# gps-tracker.net
KiCad netlist of a schematic drawn in EAGLE
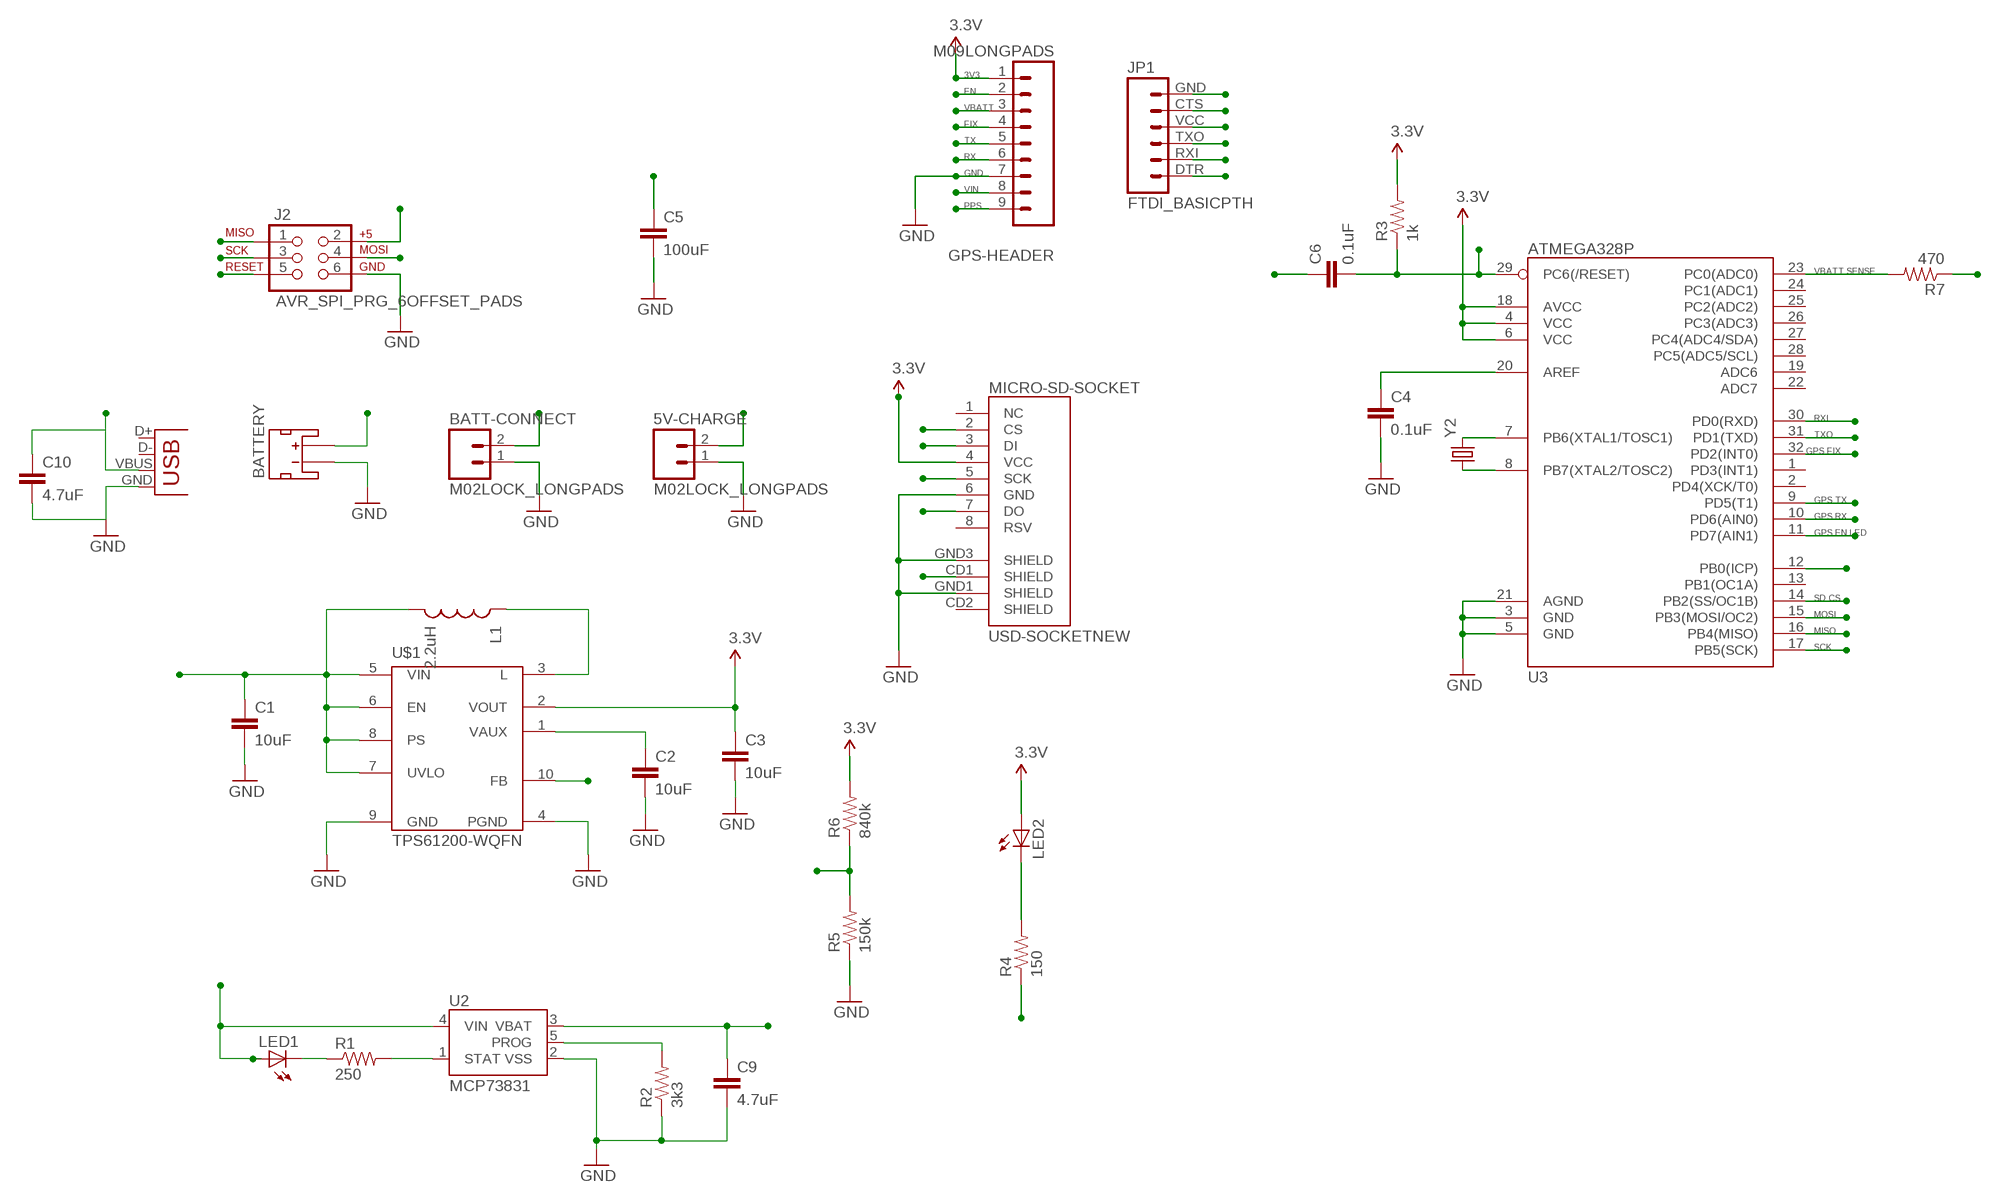
[diagram p0: schematic, sheet 1]

(export (version "E")
  (design (tool "Eeschema 10.0.6"))
  (components
    (comp (ref "5V-CHARGE")
      (value "M02LOCK_LONGPADS")
      (footprint "eagle-import:1X02_LOCK_LONGPADS")
      (libsource (lib "eagle-import") (part "M02LOCK_LONGPADS"))
    )
    (comp (ref "BATT-CONNECT")
      (value "M02LOCK_LONGPADS")
      (footprint "eagle-import:1X02_LOCK_LONGPADS")
      (libsource (lib "eagle-import") (part "M02LOCK_LONGPADS"))
    )
    (comp (ref "BATTERY")
      (value "JST_2MM_MALE")
      (footprint "eagle-import:JST-2-SMD")
      (libsource (lib "eagle-import") (part "JST_2MM_MALE"))
    )
    (comp (ref "C1")
      (value "10uF")
      (footprint "eagle-import:1206")
      (libsource (lib "eagle-import") (part "CAP1206"))
    )
    (comp (ref "C2")
      (value "10uF")
      (footprint "eagle-import:1206")
      (libsource (lib "eagle-import") (part "CAP1206"))
    )
    (comp (ref "C3")
      (value "10uF")
      (footprint "eagle-import:1206")
      (libsource (lib "eagle-import") (part "CAP1206"))
    )
    (comp (ref "C4")
      (value "0.1uF")
      (footprint "eagle-import:0603-CAP")
      (libsource (lib "eagle-import") (part "SparkFun-Capacitors_CAP0603-CAP"))
    )
    (comp (ref "C5")
      (value "100uF")
      (footprint "eagle-import:1206")
      (libsource (lib "eagle-import") (part "SparkFun-Capacitors_CAP1206"))
    )
    (comp (ref "C6")
      (value "0.1uF")
      (footprint "eagle-import:0603-CAP")
      (libsource (lib "eagle-import") (part "SparkFun-Capacitors_CAP0603-CAP"))
    )
    (comp (ref "C9")
      (value "4.7uF")
      (footprint "eagle-import:1206")
      (libsource (lib "eagle-import") (part "CAP1206"))
    )
    (comp (ref "C10")
      (value "4.7uF")
      (footprint "eagle-import:1206")
      (libsource (lib "eagle-import") (part "CAP1206"))
    )
    (comp (ref "GPS-HEADER")
      (value "M09LONGPADS")
      (footprint "eagle-import:1X09_LONGPADS")
      (libsource (lib "eagle-import") (part "M09LONGPADS"))
    )
    (comp (ref "J2")
      (value "AVR_SPI_PRG_6OFFSET_PADS")
      (footprint "eagle-import:2X3_OFFSET")
      (libsource (lib "eagle-import") (part "AVR_SPI_PRG_6OFFSET_PADS"))
    )
    (comp (ref "JP1")
      (value "FTDI_BASICPTH")
      (footprint "eagle-import:FTDI_BASIC")
      (libsource (lib "eagle-import") (part "FTDI_BASICPTH"))
    )
    (comp (ref "L1")
      (value "2.2uH")
      (footprint "eagle-import:CDRH3D28")
      (libsource (lib "eagle-import") (part "INDUCTOR-"))
    )
    (comp (ref "LED1")
      (value "LED0603")
      (footprint "eagle-import:LED-0603")
      (libsource (lib "eagle-import") (part "LED0603"))
    )
    (comp (ref "LED2")
      (value "LED5MM")
      (footprint "eagle-import:LED5MM")
      (libsource (lib "eagle-import") (part "SparkFun-LED_LED5MM"))
    )
    (comp (ref "MICRO-SD-SOCKET")
      (value "USD-SOCKETNEW")
      (footprint "eagle-import:MICRO-SD-SOCKET-PP")
      (libsource (lib "eagle-import") (part "USD-SOCKETNEW"))
    )
    (comp (ref "R1")
      (value "250")
      (footprint "eagle-import:0603-RES")
      (libsource (lib "eagle-import") (part "RESISTOR0603-RES"))
    )
    (comp (ref "R2")
      (value "3k3")
      (footprint "eagle-import:0603-RES")
      (libsource (lib "eagle-import") (part "RESISTOR0603-RES"))
    )
    (comp (ref "R3")
      (value "1k")
      (footprint "eagle-import:0805")
      (libsource (lib "eagle-import") (part "RESISTOR0805-RES"))
    )
    (comp (ref "R4")
      (value "150")
      (footprint "eagle-import:0805")
      (libsource (lib "eagle-import") (part "RESISTOR0805-RES"))
    )
    (comp (ref "R5")
      (value "150k")
      (footprint "eagle-import:0603-RES")
      (libsource (lib "eagle-import") (part "RESISTOR0603-RES"))
    )
    (comp (ref "R6")
      (value "840k")
      (footprint "eagle-import:0603-RES")
      (libsource (lib "eagle-import") (part "RESISTOR0603-RES"))
    )
    (comp (ref "R7")
      (value "470")
      (footprint "eagle-import:0805")
      (libsource (lib "eagle-import") (part "RESISTOR0805-RES"))
    )
    (comp (ref "U$1")
      (value "TPS61200-WQFN")
      (footprint "eagle-import:QFN-10")
      (libsource (lib "eagle-import") (part "TPS61200-WQFN"))
    )
    (comp (ref "U2")
      (value "MCP73831")
      (footprint "eagle-import:SOT23-5")
      (libsource (lib "eagle-import") (part "MCP73831"))
    )
    (comp (ref "U3")
      (value "ATMEGA328P")
      (footprint "eagle-import:TQFP32-08")
      (libsource (lib "eagle-import") (part "ATMEGA328_SMT"))
    )
    (comp (ref "X1")
      (value "USBSMD")
      (footprint "eagle-import:USB-MINIB")
      (libsource (lib "eagle-import") (part "USBSMD"))
    )
    (comp (ref "Y2")
      (value "CRYSTAL5X3")
      (footprint "eagle-import:CRYSTAL-SMD-5X3")
      (libsource (lib "eagle-import") (part "CRYSTAL5X3"))
    )
  )
  (nets
    (net (code "1") (name "/BATT_LED") (class "Default")
      (node (ref "R4") (pin "1") (pinfunction "1_1") (pintype "passive"))
      (node (ref "U3") (pin "12") (pinfunction "PB0(ICP)_12") (pintype "bidirectional"))
    )
    (net (code "2") (name "/DTR") (class "Default")
      (node (ref "C6") (pin "1") (pinfunction "1_1") (pintype "passive"))
      (node (ref "JP1") (pin "DTR") (pinfunction "1_DTR") (pintype "passive"))
    )
    (net (code "3") (name "/FB") (class "Default")
      (node (ref "R5") (pin "2") (pinfunction "2_2") (pintype "passive"))
      (node (ref "R6") (pin "1") (pinfunction "1_1") (pintype "passive"))
      (node (ref "U$1") (pin "10") (pinfunction "FB_10") (pintype "bidirectional"))
    )
    (net (code "4") (name "/GPS_FIX") (class "Default")
      (node (ref "GPS-HEADER") (pin "4") (pinfunction "4_4") (pintype "passive"))
      (node (ref "U3") (pin "32") (pinfunction "PD2(INT0)_32") (pintype "bidirectional"))
    )
    (net (code "5") (name "/GPS_RX") (class "Default")
      (node (ref "GPS-HEADER") (pin "6") (pinfunction "6_6") (pintype "passive"))
      (node (ref "U3") (pin "9") (pinfunction "PD5(T1)_9") (pintype "bidirectional"))
    )
    (net (code "6") (name "/GPS_TX") (class "Default")
      (node (ref "GPS-HEADER") (pin "5") (pinfunction "5_5") (pintype "passive"))
      (node (ref "U3") (pin "10") (pinfunction "PD6(AIN0)_10") (pintype "bidirectional"))
    )
    (net (code "7") (name "/MISO") (class "Default")
      (node (ref "J2") (pin "1") (pinfunction "1_1") (pintype "passive"))
      (node (ref "MICRO-SD-SOCKET") (pin "7") (pinfunction "DO_7") (pintype "bidirectional"))
      (node (ref "U3") (pin "16") (pinfunction "PB4(MISO)_16") (pintype "bidirectional"))
    )
    (net (code "8") (name "/MOSI") (class "Default")
      (node (ref "J2") (pin "4") (pinfunction "4_4") (pintype "passive"))
      (node (ref "MICRO-SD-SOCKET") (pin "3") (pinfunction "DI_3") (pintype "bidirectional"))
      (node (ref "U3") (pin "15") (pinfunction "PB3(MOSI/OC2)_15") (pintype "bidirectional"))
    )
    (net (code "9") (name "/RXI") (class "Default")
      (node (ref "JP1") (pin "TXO") (pinfunction "3_TXO") (pintype "passive"))
      (node (ref "U3") (pin "31") (pinfunction "PD1(TXD)_31") (pintype "bidirectional"))
    )
    (net (code "10") (name "/SCK") (class "Default")
      (node (ref "J2") (pin "3") (pinfunction "3_3") (pintype "passive"))
      (node (ref "MICRO-SD-SOCKET") (pin "5") (pinfunction "SCK_5") (pintype "bidirectional"))
      (node (ref "U3") (pin "17") (pinfunction "PB5(SCK)_17") (pintype "bidirectional"))
    )
    (net (code "11") (name "/SD_CS") (class "Default")
      (node (ref "MICRO-SD-SOCKET") (pin "2") (pinfunction "CS_2") (pintype "bidirectional"))
      (node (ref "U3") (pin "14") (pinfunction "PB2(SS/OC1B)_14") (pintype "bidirectional"))
    )
    (net (code "12") (name "/TXO") (class "Default")
      (node (ref "JP1") (pin "RXI") (pinfunction "2_RXI") (pintype "passive"))
      (node (ref "U3") (pin "30") (pinfunction "PD0(RXD)_30") (pintype "bidirectional"))
    )
    (net (code "13") (name "/VBATT") (class "Default")
      (node (ref "BATT-CONNECT") (pin "2") (pinfunction "2_2") (pintype "passive"))
      (node (ref "BATTERY") (pin "2") (pinfunction "+_2") (pintype "bidirectional"))
      (node (ref "C1") (pin "1") (pinfunction "1_1") (pintype "passive"))
      (node (ref "C5") (pin "1") (pinfunction "1_1") (pintype "passive"))
      (node (ref "C9") (pin "1") (pinfunction "1_1") (pintype "passive"))
      (node (ref "L1") (pin "2") (pinfunction "2_2") (pintype "passive"))
      (node (ref "R7") (pin "1") (pinfunction "1_1") (pintype "passive"))
      (node (ref "U$1") (pin "5") (pinfunction "VIN_5") (pintype "bidirectional"))
      (node (ref "U$1") (pin "6") (pinfunction "EN_6") (pintype "bidirectional"))
      (node (ref "U$1") (pin "7") (pinfunction "UVLO_7") (pintype "bidirectional"))
      (node (ref "U$1") (pin "8") (pinfunction "PS_8") (pintype "bidirectional"))
      (node (ref "U2") (pin "3") (pinfunction "VBAT_3") (pintype "power_in"))
    )
    (net (code "14") (name "/VUSB") (class "Default")
      (node (ref "5V-CHARGE") (pin "2") (pinfunction "2_2") (pintype "passive"))
      (node (ref "C10") (pin "1") (pinfunction "1_1") (pintype "passive"))
      (node (ref "LED1") (pin "A") (pinfunction "A_A") (pintype "passive"))
      (node (ref "U2") (pin "4") (pinfunction "VIN_4") (pintype "power_in"))
      (node (ref "X1") (pin "VBUS") (pinfunction "VBUS_VBUS") (pintype "bidirectional"))
    )
    (net (code "15") (name "/{slash}RESET") (class "Default")
      (node (ref "C6") (pin "2") (pinfunction "2_2") (pintype "passive"))
      (node (ref "J2") (pin "5") (pinfunction "5_5") (pintype "passive"))
      (node (ref "R3") (pin "1") (pinfunction "1_1") (pintype "passive"))
      (node (ref "U3") (pin "29") (pinfunction "PC6(/RESET)_29") (pintype "bidirectional"))
    )
    (net (code "16") (name "3.3V") (class "Default")
      (node (ref "C3") (pin "1") (pinfunction "1_1") (pintype "passive"))
      (node (ref "GPS-HEADER") (pin "1") (pinfunction "1_1") (pintype "passive"))
      (node (ref "LED2") (pin "A") (pinfunction "A_A") (pintype "passive"))
      (node (ref "MICRO-SD-SOCKET") (pin "4") (pinfunction "VCC_4") (pintype "bidirectional"))
      (node (ref "R3") (pin "2") (pinfunction "2_2") (pintype "passive"))
      (node (ref "R6") (pin "2") (pinfunction "2_2") (pintype "passive"))
      (node (ref "U$1") (pin "2") (pinfunction "VOUT_2") (pintype "bidirectional"))
      (node (ref "U3") (pin "18") (pinfunction "AVCC_18") (pintype "bidirectional"))
      (node (ref "U3") (pin "4") (pinfunction "VCC_4") (pintype "bidirectional"))
      (node (ref "U3") (pin "6") (pinfunction "VCC_6") (pintype "bidirectional"))
    )
    (net (code "17") (name "GND") (class "Default")
      (node (ref "5V-CHARGE") (pin "1") (pinfunction "1_1") (pintype "passive"))
      (node (ref "BATT-CONNECT") (pin "1") (pinfunction "1_1") (pintype "passive"))
      (node (ref "BATTERY") (pin "1") (pinfunction "-_1") (pintype "bidirectional"))
      (node (ref "C1") (pin "2") (pinfunction "2_2") (pintype "passive"))
      (node (ref "C10") (pin "2") (pinfunction "2_2") (pintype "passive"))
      (node (ref "C2") (pin "2") (pinfunction "2_2") (pintype "passive"))
      (node (ref "C3") (pin "2") (pinfunction "2_2") (pintype "passive"))
      (node (ref "C4") (pin "2") (pinfunction "2_2") (pintype "passive"))
      (node (ref "C5") (pin "2") (pinfunction "2_2") (pintype "passive"))
      (node (ref "C9") (pin "2") (pinfunction "2_2") (pintype "passive"))
      (node (ref "GPS-HEADER") (pin "7") (pinfunction "7_7") (pintype "passive"))
      (node (ref "J2") (pin "6") (pinfunction "6_6") (pintype "passive"))
      (node (ref "JP1") (pin "CTS") (pinfunction "5_CTS") (pintype "passive"))
      (node (ref "JP1") (pin "GND") (pinfunction "6_GND") (pintype "passive"))
      (node (ref "MICRO-SD-SOCKET") (pin "6") (pinfunction "GND_6") (pintype "bidirectional"))
      (node (ref "MICRO-SD-SOCKET") (pin "GND1") (pinfunction "SHIELD_GND1") (pintype "bidirectional"))
      (node (ref "MICRO-SD-SOCKET") (pin "GND3") (pinfunction "SHIELD_GND3") (pintype "bidirectional"))
      (node (ref "R2") (pin "1") (pinfunction "1_1") (pintype "passive"))
      (node (ref "R5") (pin "1") (pinfunction "1_1") (pintype "passive"))
      (node (ref "U$1") (pin "4") (pinfunction "PGND_4") (pintype "bidirectional"))
      (node (ref "U$1") (pin "9") (pinfunction "GND_9") (pintype "bidirectional"))
      (node (ref "U2") (pin "2") (pinfunction "VSS_2") (pintype "power_in"))
      (node (ref "U3") (pin "21") (pinfunction "AGND_21") (pintype "bidirectional"))
      (node (ref "U3") (pin "3") (pinfunction "GND_3") (pintype "bidirectional"))
      (node (ref "U3") (pin "5") (pinfunction "GND_5") (pintype "bidirectional"))
      (node (ref "X1") (pin "GND") (pinfunction "GND_GND") (pintype "bidirectional"))
    )
    (net (code "18") (name "Net-(LED1-PadC)") (class "Default")
      (node (ref "LED1") (pin "C") (pinfunction "C_C") (pintype "passive"))
      (node (ref "R1") (pin "1") (pinfunction "1_1") (pintype "passive"))
    )
    (net (code "19") (name "Net-(LED2-C)") (class "Default")
      (node (ref "LED2") (pin "K") (pinfunction "C_K") (pintype "passive"))
      (node (ref "R4") (pin "2") (pinfunction "2_2") (pintype "passive"))
    )
    (net (code "20") (name "Net-(U$1-L)") (class "Default")
      (node (ref "L1") (pin "1") (pinfunction "1_1") (pintype "passive"))
      (node (ref "U$1") (pin "3") (pinfunction "L_3") (pintype "bidirectional"))
    )
    (net (code "21") (name "Net-(U$1-VAUX)") (class "Default")
      (node (ref "C2") (pin "1") (pinfunction "1_1") (pintype "passive"))
      (node (ref "U$1") (pin "1") (pinfunction "VAUX_1") (pintype "bidirectional"))
    )
    (net (code "22") (name "Net-(U2-PROG)") (class "Default")
      (node (ref "R2") (pin "2") (pinfunction "2_2") (pintype "passive"))
      (node (ref "U2") (pin "5") (pinfunction "PROG_5") (pintype "input"))
    )
    (net (code "23") (name "Net-(U2-STAT)") (class "Default")
      (node (ref "R1") (pin "2") (pinfunction "2_2") (pintype "passive"))
      (node (ref "U2") (pin "1") (pinfunction "STAT_1") (pintype "output"))
    )
    (net (code "24") (name "Net-(U3-AREF)") (class "Default")
      (node (ref "C4") (pin "1") (pinfunction "1_1") (pintype "passive"))
      (node (ref "U3") (pin "20") (pinfunction "AREF_20") (pintype "bidirectional"))
    )
    (net (code "25") (name "Net-(U3-PB6(XTAL1{slash}TOSC1))") (class "Default")
      (node (ref "U3") (pin "7") (pinfunction "PB6(XTAL1/TOSC1)_7") (pintype "bidirectional"))
      (node (ref "Y2") (pin "3") (pinfunction "2_3") (pintype "passive"))
    )
    (net (code "26") (name "Net-(U3-PB7(XTAL2{slash}TOSC2))") (class "Default")
      (node (ref "U3") (pin "8") (pinfunction "PB7(XTAL2/TOSC2)_8") (pintype "bidirectional"))
      (node (ref "Y2") (pin "1") (pinfunction "1_1") (pintype "passive"))
    )
    (net (code "27") (name "Net-(U3-PC0(ADC0))") (class "Default")
      (node (ref "R7") (pin "2") (pinfunction "2_2") (pintype "passive"))
      (node (ref "U3") (pin "23") (pinfunction "PC0(ADC0)_23") (pintype "bidirectional"))
    )
    (net (code "28") (name "unconnected-(BATTERY-PAD1-PadNC1)") (class "Default")
      (node (ref "BATTERY") (pin "NC1") (pinfunction "PAD1_NC1") (pintype "bidirectional"))
    )
    (net (code "29") (name "unconnected-(BATTERY-PAD2-PadNC2)") (class "Default")
      (node (ref "BATTERY") (pin "NC2") (pinfunction "PAD2_NC2") (pintype "bidirectional"))
    )
    (net (code "30") (name "unconnected-(GPS-HEADER-Pad2)") (class "Default")
      (node (ref "GPS-HEADER") (pin "2") (pinfunction "2_2") (pintype "passive"))
    )
    (net (code "31") (name "unconnected-(GPS-HEADER-Pad3)") (class "Default")
      (node (ref "GPS-HEADER") (pin "3") (pinfunction "3_3") (pintype "passive"))
    )
    (net (code "32") (name "unconnected-(GPS-HEADER-Pad8)") (class "Default")
      (node (ref "GPS-HEADER") (pin "8") (pinfunction "8_8") (pintype "passive"))
    )
    (net (code "33") (name "unconnected-(GPS-HEADER-Pad9)") (class "Default")
      (node (ref "GPS-HEADER") (pin "9") (pinfunction "9_9") (pintype "passive"))
    )
    (net (code "34") (name "unconnected-(J2-Pad2)") (class "Default")
      (node (ref "J2") (pin "2") (pinfunction "2_2") (pintype "passive"))
    )
    (net (code "35") (name "unconnected-(JP1-4-PadVCC)") (class "Default")
      (node (ref "JP1") (pin "VCC") (pinfunction "4_VCC") (pintype "passive"))
    )
    (net (code "36") (name "unconnected-(MICRO-SD-SOCKET-NC-Pad1)") (class "Default")
      (node (ref "MICRO-SD-SOCKET") (pin "1") (pinfunction "NC_1") (pintype "bidirectional"))
    )
    (net (code "37") (name "unconnected-(MICRO-SD-SOCKET-RSV-Pad8)") (class "Default")
      (node (ref "MICRO-SD-SOCKET") (pin "8") (pinfunction "RSV_8") (pintype "bidirectional"))
    )
    (net (code "38") (name "unconnected-(MICRO-SD-SOCKET-SHIELD-PadCD1)") (class "Default")
      (node (ref "MICRO-SD-SOCKET") (pin "CD1") (pinfunction "SHIELD_CD1") (pintype "bidirectional"))
    )
    (net (code "39") (name "unconnected-(MICRO-SD-SOCKET-SHIELD-PadCD2)") (class "Default")
      (node (ref "MICRO-SD-SOCKET") (pin "CD2") (pinfunction "SHIELD_CD2") (pintype "bidirectional"))
    )
    (net (code "40") (name "unconnected-(U3-ADC6-Pad19)") (class "Default")
      (node (ref "U3") (pin "19") (pinfunction "ADC6_19") (pintype "bidirectional"))
    )
    (net (code "41") (name "unconnected-(U3-ADC7-Pad22)") (class "Default")
      (node (ref "U3") (pin "22") (pinfunction "ADC7_22") (pintype "bidirectional"))
    )
    (net (code "42") (name "unconnected-(U3-PB1(OC1A)-Pad13)") (class "Default")
      (node (ref "U3") (pin "13") (pinfunction "PB1(OC1A)_13") (pintype "bidirectional"))
    )
    (net (code "43") (name "unconnected-(U3-PC1(ADC1)-Pad24)") (class "Default")
      (node (ref "U3") (pin "24") (pinfunction "PC1(ADC1)_24") (pintype "bidirectional"))
    )
    (net (code "44") (name "unconnected-(U3-PC2(ADC2)-Pad25)") (class "Default")
      (node (ref "U3") (pin "25") (pinfunction "PC2(ADC2)_25") (pintype "bidirectional"))
    )
    (net (code "45") (name "unconnected-(U3-PC3(ADC3)-Pad26)") (class "Default")
      (node (ref "U3") (pin "26") (pinfunction "PC3(ADC3)_26") (pintype "bidirectional"))
    )
    (net (code "46") (name "unconnected-(U3-PC4(ADC4{slash}SDA)-Pad27)") (class "Default")
      (node (ref "U3") (pin "27") (pinfunction "PC4(ADC4/SDA)_27") (pintype "bidirectional"))
    )
    (net (code "47") (name "unconnected-(U3-PC5(ADC5{slash}SCL)-Pad28)") (class "Default")
      (node (ref "U3") (pin "28") (pinfunction "PC5(ADC5/SCL)_28") (pintype "bidirectional"))
    )
    (net (code "48") (name "unconnected-(U3-PD3(INT1)-Pad1)") (class "Default")
      (node (ref "U3") (pin "1") (pinfunction "PD3(INT1)_1") (pintype "bidirectional"))
    )
    (net (code "49") (name "unconnected-(U3-PD4(XCK{slash}T0)-Pad2)") (class "Default")
      (node (ref "U3") (pin "2") (pinfunction "PD4(XCK/T0)_2") (pintype "bidirectional"))
    )
    (net (code "50") (name "unconnected-(U3-PD7(AIN1)-Pad11)") (class "Default")
      (node (ref "U3") (pin "11") (pinfunction "PD7(AIN1)_11") (pintype "bidirectional"))
    )
    (net (code "51") (name "unconnected-(X1-PadD+)") (class "Default")
      (node (ref "X1") (pin "D+") (pinfunction "D+_D+") (pintype "bidirectional"))
    )
    (net (code "52") (name "unconnected-(X1-PadD-)") (class "Default")
      (node (ref "X1") (pin "D-") (pinfunction "D-_D-") (pintype "bidirectional"))
    )
  )
)
